# ProPrj__1_2024-12-26.net
KiCad netlist of a schematic drawn in EasyEDA Pro
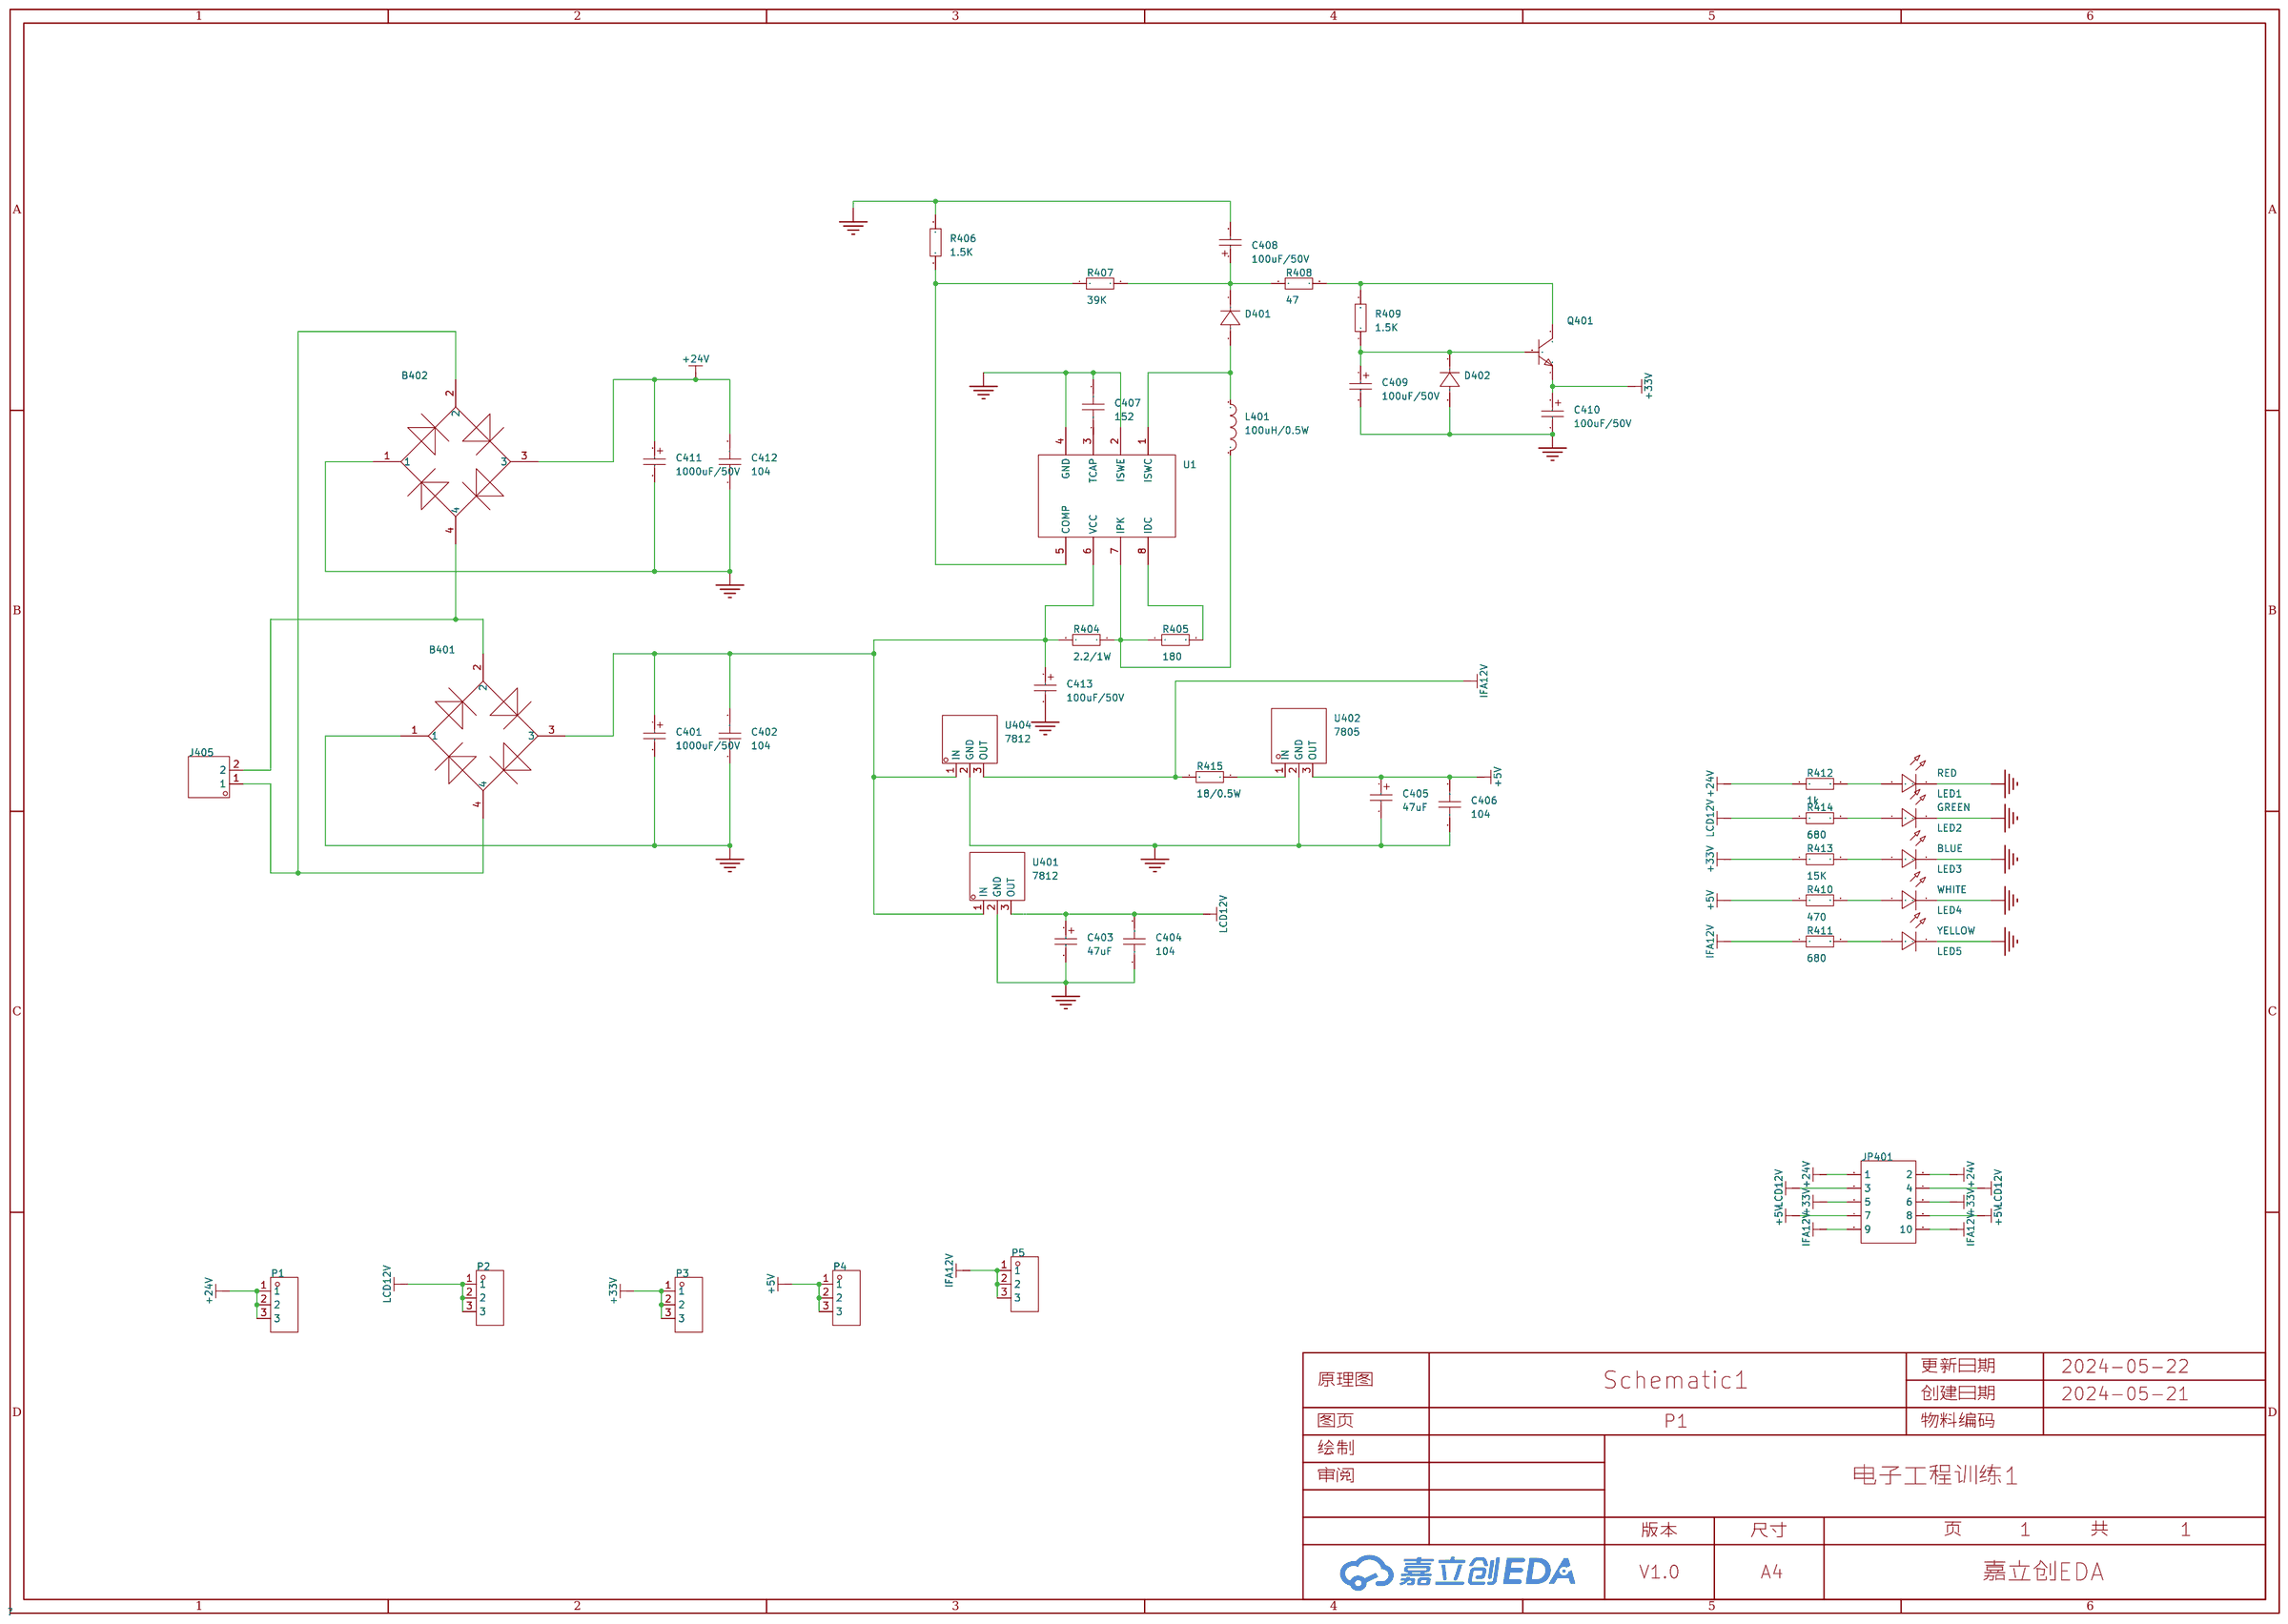
[diagram p0: schematic sheet]

(export (version "E")
  (design (tool "Eeschema 10.0.6"))
  (components
    (comp (ref "B401") (value "~") (libsource (lib "easyedapro") (part "整流桥")))
    (comp (ref "B402") (value "~") (libsource (lib "easyedapro") (part "整流桥")))
    (comp (ref "C401")
      (value "1000uF/50V")
      (footprint "easyedapro:C_Ele_SMD_3x5.4mm")
      (libsource (lib "easyedapro") (part "CAP"))
    )
    (comp (ref "C402")
      (value "104")
      (footprint "easyedapro:C0603")
      (libsource (lib "easyedapro") (part "CapAcitance"))
    )
    (comp (ref "C403")
      (value "47uF")
      (footprint "easyedapro:C_Ele_SMD_3x5.4mm")
      (libsource (lib "easyedapro") (part "CAP"))
    )
    (comp (ref "C404")
      (value "104")
      (footprint "easyedapro:C0603")
      (libsource (lib "easyedapro") (part "CapAcitance"))
    )
    (comp (ref "C405")
      (value "47uF")
      (footprint "easyedapro:C_Ele_SMD_3x5.4mm")
      (libsource (lib "easyedapro") (part "CAP"))
    )
    (comp (ref "C406")
      (value "104")
      (footprint "easyedapro:C0603")
      (libsource (lib "easyedapro") (part "CapAcitance"))
    )
    (comp (ref "C407")
      (value "152")
      (footprint "easyedapro:C0603")
      (libsource (lib "easyedapro") (part "CapAcitance"))
    )
    (comp (ref "C408")
      (value "100uF/50V")
      (footprint "easyedapro:C_Ele_SMD_3x5.4mm")
      (libsource (lib "easyedapro") (part "CAP"))
    )
    (comp (ref "C409")
      (value "100uF/50V")
      (footprint "easyedapro:C_Ele_SMD_3x5.4mm")
      (libsource (lib "easyedapro") (part "CAP"))
    )
    (comp (ref "C410")
      (value "100uF/50V")
      (footprint "easyedapro:C_Ele_SMD_3x5.4mm")
      (libsource (lib "easyedapro") (part "CAP"))
    )
    (comp (ref "C411")
      (value "1000uF/50V")
      (footprint "easyedapro:C_Ele_SMD_3x5.4mm")
      (libsource (lib "easyedapro") (part "CAP"))
    )
    (comp (ref "C412")
      (value "104")
      (footprint "easyedapro:C0603")
      (libsource (lib "easyedapro") (part "CapAcitance"))
    )
    (comp (ref "C413")
      (value "100uF/50V")
      (footprint "easyedapro:C_Ele_SMD_3x5.4mm")
      (libsource (lib "easyedapro") (part "CAP"))
    )
    (comp (ref "D401")
      (value "~")
      (footprint "easyedapro:DO_1N4007")
      (libsource (lib "easyedapro") (part "D_1N4007"))
    )
    (comp (ref "D402")
      (value "~")
      (footprint "easyedapro:DO_1N4007")
      (libsource (lib "easyedapro") (part "D_1N4007"))
    )
    (comp (ref "J405")
      (value "~")
      (footprint "easyedapro:HDR-TH_2P-P2.54-V-M-1")
      (libsource (lib "easyedapro") (part "210S-1*2P L=11.6MMGold-plated black"))
    )
    (comp (ref "JP401")
      (value "~")
      (footprint "easyedapro:HDR-TH_10P-P2.54-V-F-R2-C5-S2.54")
      (libsource (lib "easyedapro") (part "HDR-F-2.54_2x5"))
    )
    (comp (ref "L401")
      (value "100uH/0.5W")
      (footprint "easyedapro:L0603")
      (libsource (lib "easyedapro") (part "SDFL1608S100KTF"))
    )
    (comp (ref "LED1")
      (value "RED")
      (footprint "easyedapro:LED_TH-3mm")
      (libsource (lib "easyedapro") (part "LED_TH-R"))
    )
    (comp (ref "LED2")
      (value "GREEN")
      (footprint "easyedapro:LED_TH-3mm")
      (libsource (lib "easyedapro") (part "LED_TH-R"))
    )
    (comp (ref "LED3")
      (value "BLUE")
      (footprint "easyedapro:LED_TH-3mm")
      (libsource (lib "easyedapro") (part "LED_TH-R"))
    )
    (comp (ref "LED4")
      (value "WHITE")
      (footprint "easyedapro:LED_TH-3mm")
      (libsource (lib "easyedapro") (part "LED_TH-R"))
    )
    (comp (ref "LED5")
      (value "YELLOW")
      (footprint "easyedapro:LED_TH-3mm")
      (libsource (lib "easyedapro") (part "LED_TH-R"))
    )
    (comp (ref "P1")
      (value "~")
      (footprint "easyedapro:HDR-TH_3P-P2.54-V-F")
      (libsource (lib "easyedapro") (part "PM254V-11-03-H85"))
    )
    (comp (ref "P2")
      (value "~")
      (footprint "easyedapro:HDR-TH_3P-P2.54-V-F")
      (libsource (lib "easyedapro") (part "PM254V-11-03-H85"))
    )
    (comp (ref "P3")
      (value "~")
      (footprint "easyedapro:HDR-TH_3P-P2.54-V-F")
      (libsource (lib "easyedapro") (part "PM254V-11-03-H85"))
    )
    (comp (ref "P4")
      (value "~")
      (footprint "easyedapro:HDR-TH_3P-P2.54-V-F")
      (libsource (lib "easyedapro") (part "PM254V-11-03-H85"))
    )
    (comp (ref "P5")
      (value "~")
      (footprint "easyedapro:HDR-TH_3P-P2.54-V-F")
      (libsource (lib "easyedapro") (part "PM254V-11-03-H85"))
    )
    (comp (ref "Q401")
      (value "~")
      (footprint "easyedapro:S8050_SOT-23")
      (libsource (lib "easyedapro") (part "NPN"))
    )
    (comp (ref "R404")
      (value "2.2/1W")
      (footprint "easyedapro:Res_1/4W")
      (libsource (lib "easyedapro") (part "电阻"))
    )
    (comp (ref "R405")
      (value "180")
      (footprint "easyedapro:Res_1/4W")
      (libsource (lib "easyedapro") (part "电阻"))
    )
    (comp (ref "R406")
      (value "1.5K")
      (footprint "easyedapro:Res_1/4W")
      (libsource (lib "easyedapro") (part "电阻"))
    )
    (comp (ref "R407")
      (value "39K")
      (footprint "easyedapro:Res_1/4W")
      (libsource (lib "easyedapro") (part "电阻"))
    )
    (comp (ref "R408")
      (value "47")
      (footprint "easyedapro:Res_1/4W")
      (libsource (lib "easyedapro") (part "电阻"))
    )
    (comp (ref "R409")
      (value "1.5K")
      (footprint "easyedapro:Res_1/4W")
      (libsource (lib "easyedapro") (part "电阻"))
    )
    (comp (ref "R410")
      (value "470")
      (footprint "easyedapro:Res_1/4W")
      (libsource (lib "easyedapro") (part "电阻"))
    )
    (comp (ref "R411")
      (value "680")
      (footprint "easyedapro:Res_1/4W")
      (libsource (lib "easyedapro") (part "电阻"))
    )
    (comp (ref "R412")
      (value "1k")
      (footprint "easyedapro:Res_1/4W")
      (libsource (lib "easyedapro") (part "电阻"))
    )
    (comp (ref "R413")
      (value "15K")
      (footprint "easyedapro:Res_1/4W")
      (libsource (lib "easyedapro") (part "电阻"))
    )
    (comp (ref "R414")
      (value "680")
      (footprint "easyedapro:Res_1/4W")
      (libsource (lib "easyedapro") (part "电阻"))
    )
    (comp (ref "R415")
      (value "18/0.5W")
      (footprint "easyedapro:Res_1/4W")
      (libsource (lib "easyedapro") (part "电阻"))
    )
    (comp (ref "U1") (value "~") (libsource (lib "easyedapro") (part "MC34063")))
    (comp (ref "U401")
      (value "7812")
      (footprint "easyedapro:TO-220-3_L10.0-W4.5-P2.54-L")
      (description "输出类型:固定;最大输入电压:35V;输出电压:12V;最大输出电流:1.5A;电源纹波抑制比(PSRR):55dB@(120Hz);输出极性:正极;")
      (fields (field (name "Manufacturer") "BLUE ROCKET(蓝箭)"))
      (libsource (lib "easyedapro") (part "7812"))
    )
    (comp (ref "U402")
      (value "7805")
      (footprint "easyedapro:TO-220-3_L10.2-W4.5-P2.54-L-1")
      (description "输出类型:固定;最大输入电压:35V;输出电压:5V;最大输出电流:1.5A;电源纹波抑制比(PSRR):62dB@(120Hz);输出极性:正极;")
      (fields (field (name "Manufacturer") "SY(顺烨）"))
      (libsource (lib "easyedapro") (part "7805_C4944936"))
    )
    (comp (ref "U404")
      (value "7812")
      (footprint "easyedapro:TO-220-3_L10.0-W4.5-P2.54-L")
      (description "输出类型:固定;最大输入电压:35V;输出电压:12V;最大输出电流:1.5A;电源纹波抑制比(PSRR):55dB@(120Hz);输出极性:正极;")
      (fields (field (name "Manufacturer") "BLUE ROCKET(蓝箭)"))
      (libsource (lib "easyedapro") (part "7812"))
    )
  )
  (nets
    (net (code "1") (name "+5V") (class "Default")
      (node (ref "C405") (pin "1") (pinfunction "1_1") (pintype "input"))
      (node (ref "C406") (pin "2") (pinfunction "2_2") (pintype "input"))
      (node (ref "JP401") (pin "7") (pinfunction "7_7") (pintype "input"))
      (node (ref "JP401") (pin "8") (pinfunction "8_8") (pintype "input"))
      (node (ref "P4") (pin "1") (pinfunction "1_1") (pintype "unspecified"))
      (node (ref "P4") (pin "2") (pinfunction "2_2") (pintype "unspecified"))
      (node (ref "P4") (pin "3") (pinfunction "3_3") (pintype "unspecified"))
      (node (ref "R410") (pin "1") (pinfunction "1_1") (pintype "input"))
      (node (ref "U402") (pin "3") (pinfunction "OUT_3") (pintype "unspecified"))
    )
    (net (code "2") (name "+24V") (class "Default")
      (node (ref "B402") (pin "3") (pinfunction "3_3") (pintype "input"))
      (node (ref "C411") (pin "1") (pinfunction "1_1") (pintype "input"))
      (node (ref "C412") (pin "2") (pinfunction "2_2") (pintype "input"))
      (node (ref "JP401") (pin "1") (pinfunction "1_1") (pintype "input"))
      (node (ref "JP401") (pin "2") (pinfunction "2_2") (pintype "input"))
      (node (ref "P1") (pin "1") (pinfunction "1_1") (pintype "unspecified"))
      (node (ref "P1") (pin "2") (pinfunction "2_2") (pintype "unspecified"))
      (node (ref "P1") (pin "3") (pinfunction "3_3") (pintype "unspecified"))
      (node (ref "R412") (pin "1") (pinfunction "1_1") (pintype "input"))
    )
    (net (code "3") (name "+33V") (class "Default")
      (node (ref "C410") (pin "1") (pinfunction "1_1") (pintype "input"))
      (node (ref "JP401") (pin "5") (pinfunction "5_5") (pintype "input"))
      (node (ref "JP401") (pin "6") (pinfunction "6_6") (pintype "input"))
      (node (ref "P3") (pin "1") (pinfunction "1_1") (pintype "unspecified"))
      (node (ref "P3") (pin "2") (pinfunction "2_2") (pintype "unspecified"))
      (node (ref "P3") (pin "3") (pinfunction "3_3") (pintype "unspecified"))
      (node (ref "Q401") (pin "1") (pinfunction "1_1") (pintype "unspecified"))
      (node (ref "R413") (pin "1") (pinfunction "1_1") (pintype "input"))
    )
    (net (code "4") (name "GND") (class "Default")
      (node (ref "B401") (pin "1") (pinfunction "1_1") (pintype "input"))
      (node (ref "B402") (pin "1") (pinfunction "1_1") (pintype "input"))
      (node (ref "C401") (pin "2") (pinfunction "2_2") (pintype "input"))
      (node (ref "C402") (pin "1") (pinfunction "1_1") (pintype "input"))
      (node (ref "C403") (pin "2") (pinfunction "2_2") (pintype "input"))
      (node (ref "C404") (pin "1") (pinfunction "1_1") (pintype "input"))
      (node (ref "C405") (pin "2") (pinfunction "2_2") (pintype "input"))
      (node (ref "C406") (pin "1") (pinfunction "1_1") (pintype "input"))
      (node (ref "C407") (pin "2") (pinfunction "2_2") (pintype "input"))
      (node (ref "C408") (pin "2") (pinfunction "2_2") (pintype "input"))
      (node (ref "C409") (pin "2") (pinfunction "2_2") (pintype "input"))
      (node (ref "C410") (pin "2") (pinfunction "2_2") (pintype "input"))
      (node (ref "C411") (pin "2") (pinfunction "2_2") (pintype "input"))
      (node (ref "C412") (pin "1") (pinfunction "1_1") (pintype "input"))
      (node (ref "C413") (pin "2") (pinfunction "2_2") (pintype "input"))
      (node (ref "D402") (pin "2") (pinfunction "A_2") (pintype "input"))
      (node (ref "LED1") (pin "2") (pinfunction "A_2") (pintype "input"))
      (node (ref "LED2") (pin "2") (pinfunction "A_2") (pintype "input"))
      (node (ref "LED3") (pin "2") (pinfunction "A_2") (pintype "input"))
      (node (ref "LED4") (pin "2") (pinfunction "A_2") (pintype "input"))
      (node (ref "LED5") (pin "2") (pinfunction "A_2") (pintype "input"))
      (node (ref "R406") (pin "2") (pinfunction "2_2") (pintype "input"))
      (node (ref "U1") (pin "2") (pinfunction "ISWE_2") (pintype "input"))
      (node (ref "U1") (pin "4") (pinfunction "GND_4") (pintype "input"))
      (node (ref "U401") (pin "2") (pinfunction "GND_2") (pintype "unspecified"))
      (node (ref "U402") (pin "2") (pinfunction "GND_2") (pintype "unspecified"))
      (node (ref "U404") (pin "2") (pinfunction "GND_2") (pintype "unspecified"))
    )
    (net (code "5") (name "IFA12V") (class "Default")
      (node (ref "JP401") (pin "10") (pinfunction "10_10") (pintype "input"))
      (node (ref "JP401") (pin "9") (pinfunction "9_9") (pintype "input"))
      (node (ref "P5") (pin "1") (pinfunction "1_1") (pintype "unspecified"))
      (node (ref "P5") (pin "2") (pinfunction "2_2") (pintype "unspecified"))
      (node (ref "P5") (pin "3") (pinfunction "3_3") (pintype "unspecified"))
      (node (ref "R411") (pin "1") (pinfunction "1_1") (pintype "input"))
      (node (ref "R415") (pin "2") (pinfunction "2_2") (pintype "input"))
      (node (ref "U404") (pin "3") (pinfunction "OUT_3") (pintype "unspecified"))
    )
    (net (code "6") (name "LCD12V") (class "Default")
      (node (ref "C403") (pin "1") (pinfunction "1_1") (pintype "input"))
      (node (ref "C404") (pin "2") (pinfunction "2_2") (pintype "input"))
      (node (ref "JP401") (pin "3") (pinfunction "3_3") (pintype "input"))
      (node (ref "JP401") (pin "4") (pinfunction "4_4") (pintype "input"))
      (node (ref "P2") (pin "1") (pinfunction "1_1") (pintype "unspecified"))
      (node (ref "P2") (pin "2") (pinfunction "2_2") (pintype "unspecified"))
      (node (ref "P2") (pin "3") (pinfunction "3_3") (pintype "unspecified"))
      (node (ref "R414") (pin "1") (pinfunction "1_1") (pintype "input"))
      (node (ref "U401") (pin "3") (pinfunction "OUT_3") (pintype "unspecified"))
    )
    (net (code "7") (name "Net-(B401-Pad2)") (class "Default")
      (node (ref "B401") (pin "2") (pinfunction "2_2") (pintype "input"))
      (node (ref "B402") (pin "4") (pinfunction "4_4") (pintype "input"))
      (node (ref "J405") (pin "2") (pinfunction "2_2") (pintype "unspecified"))
    )
    (net (code "8") (name "Net-(B401-Pad4)") (class "Default")
      (node (ref "B401") (pin "4") (pinfunction "4_4") (pintype "input"))
      (node (ref "B402") (pin "2") (pinfunction "2_2") (pintype "input"))
      (node (ref "J405") (pin "1") (pinfunction "1_1") (pintype "unspecified"))
    )
    (net (code "9") (name "Net-(D401-A)") (class "Default")
      (node (ref "D401") (pin "2") (pinfunction "A_2") (pintype "input"))
      (node (ref "L401") (pin "1") (pinfunction "1_1") (pintype "unspecified"))
      (node (ref "U1") (pin "1") (pinfunction "ISWC_1") (pintype "input"))
    )
    (net (code "10") (name "Net-(D401-K)") (class "Default")
      (node (ref "C408") (pin "1") (pinfunction "1_1") (pintype "input"))
      (node (ref "D401") (pin "1") (pinfunction "K_1") (pintype "input"))
      (node (ref "R407") (pin "2") (pinfunction "2_2") (pintype "input"))
      (node (ref "R408") (pin "1") (pinfunction "1_1") (pintype "input"))
    )
    (net (code "11") (name "Net-(D402-K)") (class "Default")
      (node (ref "C409") (pin "1") (pinfunction "1_1") (pintype "input"))
      (node (ref "D402") (pin "1") (pinfunction "K_1") (pintype "input"))
      (node (ref "Q401") (pin "3") (pinfunction "3_3") (pintype "unspecified"))
      (node (ref "R409") (pin "1") (pinfunction "1_1") (pintype "input"))
    )
    (net (code "12") (name "Net-(LED1-C)") (class "Default")
      (node (ref "LED1") (pin "1") (pinfunction "C_1") (pintype "input"))
      (node (ref "R412") (pin "2") (pinfunction "2_2") (pintype "input"))
    )
    (net (code "13") (name "Net-(LED2-C)") (class "Default")
      (node (ref "LED2") (pin "1") (pinfunction "C_1") (pintype "input"))
      (node (ref "R414") (pin "2") (pinfunction "2_2") (pintype "input"))
    )
    (net (code "14") (name "Net-(LED3-C)") (class "Default")
      (node (ref "LED3") (pin "1") (pinfunction "C_1") (pintype "input"))
      (node (ref "R413") (pin "2") (pinfunction "2_2") (pintype "input"))
    )
    (net (code "15") (name "Net-(LED4-C)") (class "Default")
      (node (ref "LED4") (pin "1") (pinfunction "C_1") (pintype "input"))
      (node (ref "R410") (pin "2") (pinfunction "2_2") (pintype "input"))
    )
    (net (code "16") (name "Net-(LED5-C)") (class "Default")
      (node (ref "LED5") (pin "1") (pinfunction "C_1") (pintype "input"))
      (node (ref "R411") (pin "2") (pinfunction "2_2") (pintype "input"))
    )
    (net (code "17") (name "Net-(Q401-Pad2)") (class "Default")
      (node (ref "Q401") (pin "2") (pinfunction "2_2") (pintype "unspecified"))
      (node (ref "R408") (pin "2") (pinfunction "2_2") (pintype "input"))
      (node (ref "R409") (pin "2") (pinfunction "2_2") (pintype "input"))
    )
    (net (code "18") (name "Net-(U1-COMP)") (class "Default")
      (node (ref "R406") (pin "1") (pinfunction "1_1") (pintype "input"))
      (node (ref "R407") (pin "1") (pinfunction "1_1") (pintype "input"))
      (node (ref "U1") (pin "5") (pinfunction "COMP_5") (pintype "input"))
    )
    (net (code "19") (name "Net-(U1-IDC)") (class "Default")
      (node (ref "R405") (pin "2") (pinfunction "2_2") (pintype "input"))
      (node (ref "U1") (pin "8") (pinfunction "IDC_8") (pintype "input"))
    )
    (net (code "20") (name "Net-(U1-IPK)") (class "Default")
      (node (ref "L401") (pin "2") (pinfunction "2_2") (pintype "unspecified"))
      (node (ref "R404") (pin "1") (pinfunction "1_1") (pintype "input"))
      (node (ref "R405") (pin "1") (pinfunction "1_1") (pintype "input"))
      (node (ref "U1") (pin "7") (pinfunction "IPK_7") (pintype "input"))
    )
    (net (code "21") (name "Net-(U1-TCAP)") (class "Default")
      (node (ref "C407") (pin "1") (pinfunction "1_1") (pintype "input"))
      (node (ref "U1") (pin "3") (pinfunction "TCAP_3") (pintype "input"))
    )
    (net (code "22") (name "Net-(U1-VCC)") (class "Default")
      (node (ref "B401") (pin "3") (pinfunction "3_3") (pintype "input"))
      (node (ref "C401") (pin "1") (pinfunction "1_1") (pintype "input"))
      (node (ref "C402") (pin "2") (pinfunction "2_2") (pintype "input"))
      (node (ref "C413") (pin "1") (pinfunction "1_1") (pintype "input"))
      (node (ref "R404") (pin "2") (pinfunction "2_2") (pintype "input"))
      (node (ref "U1") (pin "6") (pinfunction "VCC_6") (pintype "input"))
      (node (ref "U401") (pin "1") (pinfunction "IN_1") (pintype "unspecified"))
      (node (ref "U404") (pin "1") (pinfunction "IN_1") (pintype "unspecified"))
    )
    (net (code "23") (name "Net-(U402-IN)") (class "Default")
      (node (ref "R415") (pin "1") (pinfunction "1_1") (pintype "input"))
      (node (ref "U402") (pin "1") (pinfunction "IN_1") (pintype "unspecified"))
    )
  )
)
